# simple_ladder_filter.net
KiCad netlist of a schematic drawn in EAGLE
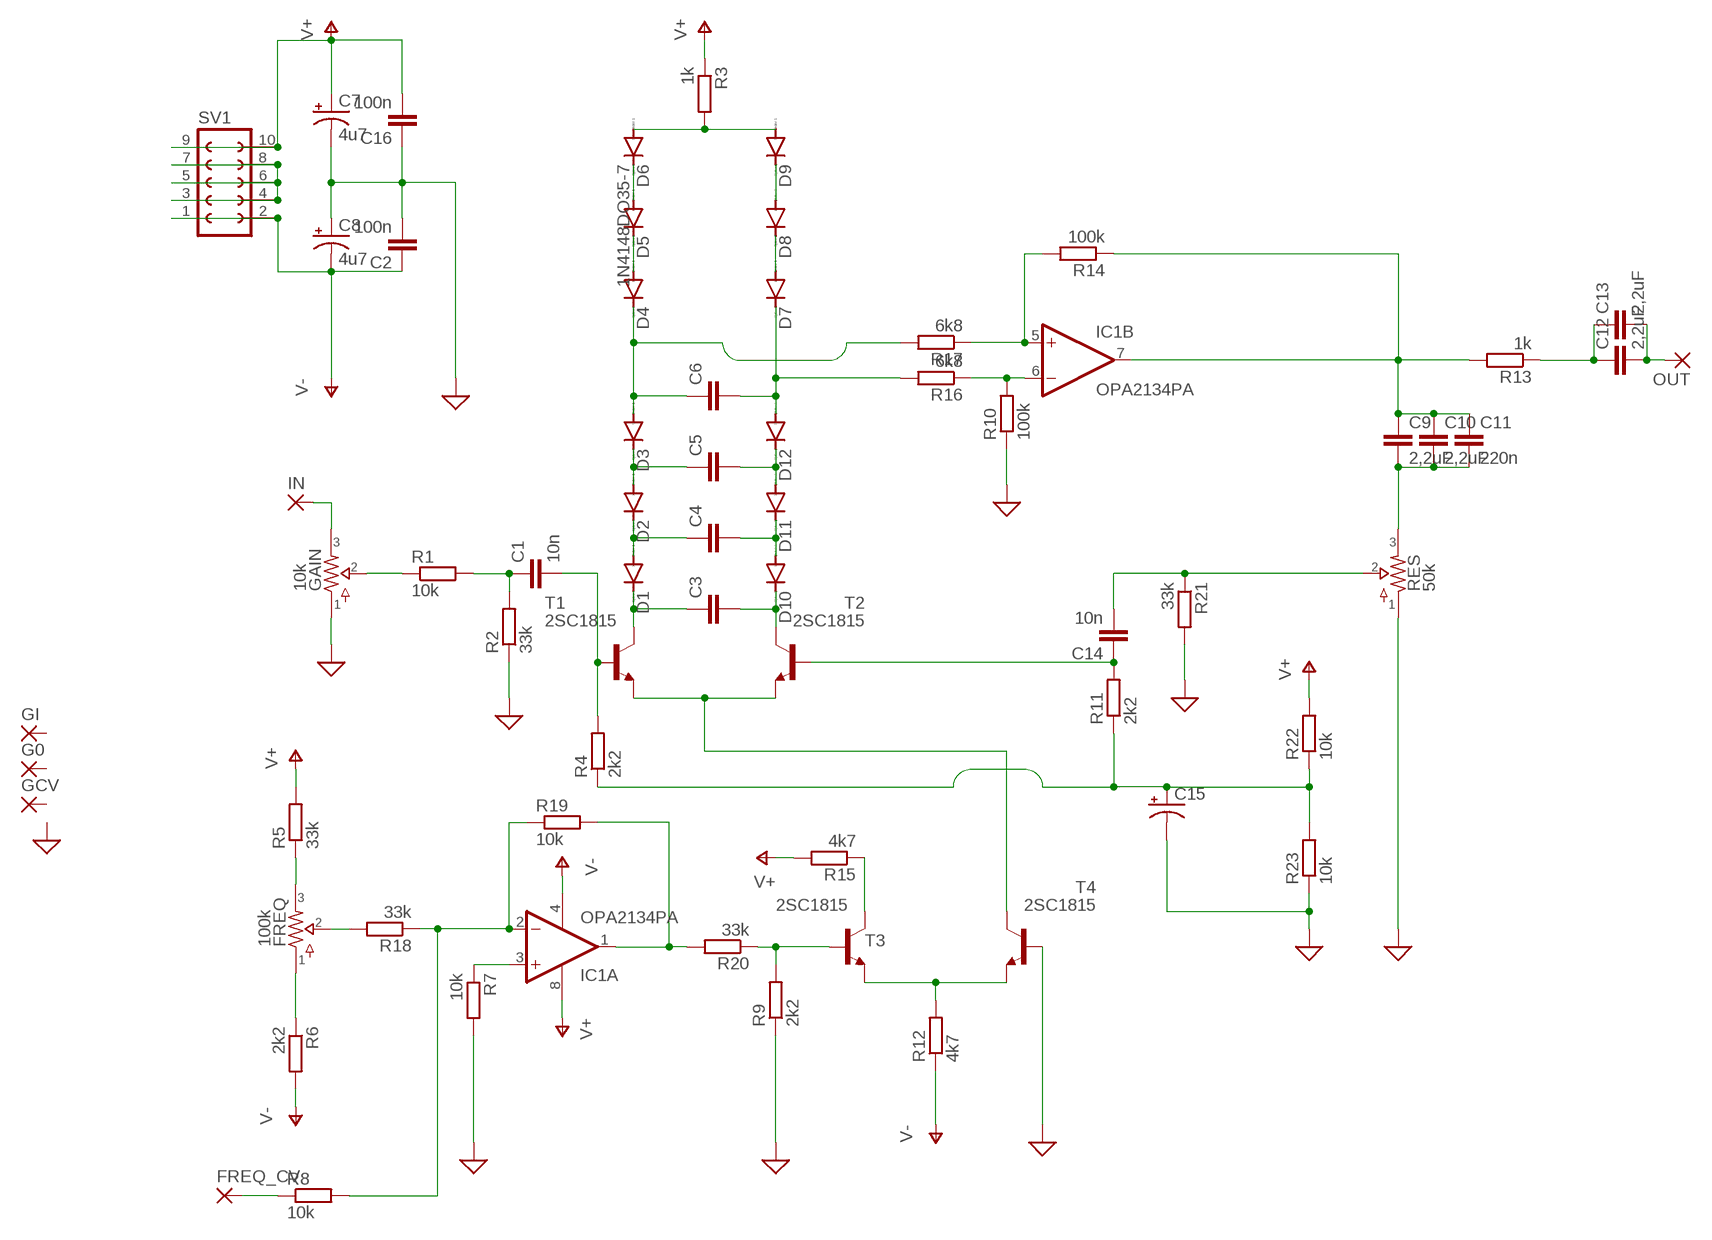
[diagram p0: schematic, sheet 1]

(export (version "E")
  (design (tool "Eeschema 10.0.6"))
  (components
    (comp (ref "C1")
      (value "10n")
      (footprint "eagle-import:C5B3")
      (libsource (lib "eagle-import") (part "C5/3"))
    )
    (comp (ref "C2")
      (value "100n")
      (footprint "eagle-import:C5B3")
      (libsource (lib "eagle-import") (part "C5/3"))
    )
    (comp (ref "C3")
      (value "C2.5/2")
      (footprint "eagle-import:C2.5-2")
      (libsource (lib "eagle-import") (part "C2.5/2"))
    )
    (comp (ref "C4")
      (value "C2.5/2")
      (footprint "eagle-import:C2.5-2")
      (libsource (lib "eagle-import") (part "C2.5/2"))
    )
    (comp (ref "C5")
      (value "C2.5/2")
      (footprint "eagle-import:C2.5-2")
      (libsource (lib "eagle-import") (part "C2.5/2"))
    )
    (comp (ref "C6")
      (value "C2.5/2")
      (footprint "eagle-import:C2.5-2")
      (libsource (lib "eagle-import") (part "C2.5/2"))
    )
    (comp (ref "C7")
      (value "4u7")
      (footprint "eagle-import:E2-4")
      (libsource (lib "eagle-import") (part "CPOL-USE2-4"))
    )
    (comp (ref "C8")
      (value "4u7")
      (footprint "eagle-import:E2-4")
      (libsource (lib "eagle-import") (part "CPOL-USE2-4"))
    )
    (comp (ref "C9")
      (value "2,2uF")
      (footprint "eagle-import:C5B5.5")
      (libsource (lib "eagle-import") (part "C5/5.5"))
    )
    (comp (ref "C10")
      (value "2,2uF")
      (footprint "eagle-import:C5B5.5")
      (libsource (lib "eagle-import") (part "C5/5.5"))
    )
    (comp (ref "C11")
      (value "220n")
      (footprint "eagle-import:C5B3")
      (libsource (lib "eagle-import") (part "C5/3"))
    )
    (comp (ref "C12")
      (value "2,2uF")
      (footprint "eagle-import:C5B5.5")
      (libsource (lib "eagle-import") (part "C5/5.5"))
    )
    (comp (ref "C13")
      (value "2,2uF")
      (footprint "eagle-import:C5B5.5")
      (libsource (lib "eagle-import") (part "C5/5.5"))
    )
    (comp (ref "C14")
      (value "10n")
      (footprint "eagle-import:C5B3")
      (libsource (lib "eagle-import") (part "C5/3"))
    )
    (comp (ref "C15")
      (value "CPOL-USE2-4")
      (footprint "eagle-import:E2-4")
      (libsource (lib "eagle-import") (part "CPOL-USE2-4"))
    )
    (comp (ref "C16")
      (value "100n")
      (footprint "eagle-import:C5B3")
      (libsource (lib "eagle-import") (part "C5/3"))
    )
    (comp (ref "D1")
      (value "1N4148DO35-7")
      (footprint "eagle-import:DO35-7")
      (libsource (lib "eagle-import") (part "1N4148DO35-7"))
    )
    (comp (ref "D2")
      (value "1N4148DO35-7")
      (footprint "eagle-import:DO35-7")
      (libsource (lib "eagle-import") (part "1N4148DO35-7"))
    )
    (comp (ref "D3")
      (value "1N4148DO35-7")
      (footprint "eagle-import:DO35-7")
      (libsource (lib "eagle-import") (part "1N4148DO35-7"))
    )
    (comp (ref "D4")
      (value "1N4148DO35-7")
      (footprint "eagle-import:DO35-7")
      (libsource (lib "eagle-import") (part "1N4148DO35-7"))
    )
    (comp (ref "D5")
      (value "1N4148DO35-7")
      (footprint "eagle-import:DO35-7")
      (libsource (lib "eagle-import") (part "1N4148DO35-7"))
    )
    (comp (ref "D6")
      (value "1N4148DO35-7")
      (footprint "eagle-import:DO35-7")
      (libsource (lib "eagle-import") (part "1N4148DO35-7"))
    )
    (comp (ref "D7")
      (value "1N4148DO35-7")
      (footprint "eagle-import:DO35-7")
      (libsource (lib "eagle-import") (part "1N4148DO35-7"))
    )
    (comp (ref "D8")
      (value "1N4148DO35-7")
      (footprint "eagle-import:DO35-7")
      (libsource (lib "eagle-import") (part "1N4148DO35-7"))
    )
    (comp (ref "D9")
      (value "1N4148DO35-7")
      (footprint "eagle-import:DO35-7")
      (libsource (lib "eagle-import") (part "1N4148DO35-7"))
    )
    (comp (ref "D10")
      (value "1N4148DO35-7")
      (footprint "eagle-import:DO35-7")
      (libsource (lib "eagle-import") (part "1N4148DO35-7"))
    )
    (comp (ref "D11")
      (value "1N4148DO35-7")
      (footprint "eagle-import:DO35-7")
      (libsource (lib "eagle-import") (part "1N4148DO35-7"))
    )
    (comp (ref "D12")
      (value "1N4148DO35-7")
      (footprint "eagle-import:DO35-7")
      (libsource (lib "eagle-import") (part "1N4148DO35-7"))
    )
    (comp (ref "FREQ")
      (value "100k")
      (footprint "eagle-import:9MM_VERT")
      (libsource (lib "eagle-import") (part "POTS9MM_VERT"))
    )
    (comp (ref "FREQ_CV")
      (value "1,6/0,9")
      (footprint "eagle-import:1,6_0,9")
      (libsource (lib "eagle-import") (part "1,6/0,9"))
    )
    (comp (ref "G0")
      (value "1,6/0,9")
      (footprint "eagle-import:1,6_0,9")
      (libsource (lib "eagle-import") (part "1,6/0,9"))
    )
    (comp (ref "GAIN")
      (value "10k")
      (footprint "eagle-import:9MM_VERT")
      (libsource (lib "eagle-import") (part "POTS9MM_VERT"))
    )
    (comp (ref "GCV")
      (value "1,6/0,9")
      (footprint "eagle-import:1,6_0,9")
      (libsource (lib "eagle-import") (part "1,6/0,9"))
    )
    (comp (ref "GI")
      (value "1,6/0,9")
      (footprint "eagle-import:1,6_0,9")
      (libsource (lib "eagle-import") (part "1,6/0,9"))
    )
    (comp (ref "IC1")
      (value "OPA2134PA")
      (footprint "eagle-import:DIL08")
      (libsource (lib "eagle-import") (part "OPA2PA134"))
    )
    (comp (ref "IN")
      (value "1,6/0,9")
      (footprint "eagle-import:1,6_0,9")
      (libsource (lib "eagle-import") (part "1,6/0,9"))
    )
    (comp (ref "OUT")
      (value "1,6/0,9")
      (footprint "eagle-import:1,6_0,9")
      (libsource (lib "eagle-import") (part "1,6/0,9"))
    )
    (comp (ref "R1")
      (value "10k")
      (footprint "eagle-import:0204_7")
      (libsource (lib "eagle-import") (part "R-EU_0204/7"))
    )
    (comp (ref "R2")
      (value "33k")
      (footprint "eagle-import:0204_7")
      (libsource (lib "eagle-import") (part "R-EU_0204/7"))
    )
    (comp (ref "R3")
      (value "1k")
      (footprint "eagle-import:0204_7")
      (libsource (lib "eagle-import") (part "R-EU_0204/7"))
    )
    (comp (ref "R4")
      (value "2k2")
      (footprint "eagle-import:0204_7")
      (libsource (lib "eagle-import") (part "R-EU_0204/7"))
    )
    (comp (ref "R5")
      (value "33k")
      (footprint "eagle-import:0204_7")
      (libsource (lib "eagle-import") (part "R-EU_0204/7"))
    )
    (comp (ref "R6")
      (value "2k2")
      (footprint "eagle-import:0204_7")
      (libsource (lib "eagle-import") (part "R-EU_0204/7"))
    )
    (comp (ref "R7")
      (value "10k")
      (footprint "eagle-import:0204_7")
      (libsource (lib "eagle-import") (part "R-EU_0204/7"))
    )
    (comp (ref "R8")
      (value "10k")
      (footprint "eagle-import:0204_7")
      (libsource (lib "eagle-import") (part "R-EU_0204/7"))
    )
    (comp (ref "R9")
      (value "2k2")
      (footprint "eagle-import:0204_7")
      (libsource (lib "eagle-import") (part "R-EU_0204/7"))
    )
    (comp (ref "R10")
      (value "100k")
      (footprint "eagle-import:0204_7")
      (libsource (lib "eagle-import") (part "R-EU_0204/7"))
    )
    (comp (ref "R11")
      (value "2k2")
      (footprint "eagle-import:0204_7")
      (libsource (lib "eagle-import") (part "R-EU_0204/7"))
    )
    (comp (ref "R12")
      (value "4k7")
      (footprint "eagle-import:0204_7")
      (libsource (lib "eagle-import") (part "R-EU_0204/7"))
    )
    (comp (ref "R13")
      (value "1k")
      (footprint "eagle-import:0204_7")
      (libsource (lib "eagle-import") (part "R-EU_0204/7"))
    )
    (comp (ref "R14")
      (value "100k")
      (footprint "eagle-import:0204_7")
      (libsource (lib "eagle-import") (part "R-EU_0204/7"))
    )
    (comp (ref "R15")
      (value "4k7")
      (footprint "eagle-import:0204_7")
      (libsource (lib "eagle-import") (part "R-EU_0204/7"))
    )
    (comp (ref "R16")
      (value "6k8")
      (footprint "eagle-import:0204_7")
      (libsource (lib "eagle-import") (part "R-EU_0204/7"))
    )
    (comp (ref "R17")
      (value "6k8")
      (footprint "eagle-import:0204_7")
      (libsource (lib "eagle-import") (part "R-EU_0204/7"))
    )
    (comp (ref "R18")
      (value "33k")
      (footprint "eagle-import:0204_7")
      (libsource (lib "eagle-import") (part "R-EU_0204/7"))
    )
    (comp (ref "R19")
      (value "10k")
      (footprint "eagle-import:0204_7")
      (libsource (lib "eagle-import") (part "R-EU_0204/7"))
    )
    (comp (ref "R20")
      (value "33k")
      (footprint "eagle-import:0204_7")
      (libsource (lib "eagle-import") (part "R-EU_0204/7"))
    )
    (comp (ref "R21")
      (value "33k")
      (footprint "eagle-import:0204_7")
      (libsource (lib "eagle-import") (part "R-EU_0204/7"))
    )
    (comp (ref "R22")
      (value "10k")
      (footprint "eagle-import:0204_7")
      (libsource (lib "eagle-import") (part "R-EU_0204/7"))
    )
    (comp (ref "R23")
      (value "10k")
      (footprint "eagle-import:0204_7")
      (libsource (lib "eagle-import") (part "R-EU_0204/7"))
    )
    (comp (ref "RES")
      (value "50k")
      (footprint "eagle-import:9MM_VERT")
      (libsource (lib "eagle-import") (part "POTS9MM_VERT"))
    )
    (comp (ref "SV1")
      (value "FE05-2")
      (footprint "eagle-import:FE05-2")
      (libsource (lib "eagle-import") (part "FE05-2"))
    )
    (comp (ref "T1")
      (value "2SC1815")
      (footprint "eagle-import:TO92-ECB")
      (libsource (lib "eagle-import") (part "2SC1815"))
    )
    (comp (ref "T2")
      (value "2SC1815")
      (footprint "eagle-import:TO92-ECB")
      (libsource (lib "eagle-import") (part "2SC1815"))
    )
    (comp (ref "T3")
      (value "2SC1815")
      (footprint "eagle-import:TO92-ECB")
      (libsource (lib "eagle-import") (part "2SC1815"))
    )
    (comp (ref "T4")
      (value "2SC1815")
      (footprint "eagle-import:TO92-ECB")
      (libsource (lib "eagle-import") (part "2SC1815"))
    )
  )
  (nets
    (net (code "1") (name "Net-(C1-Pad1)") (class "Default")
      (node (ref "C1") (pin "1") (pinfunction "1_1") (pintype "passive"))
      (node (ref "R1") (pin "2") (pinfunction "2_2") (pintype "passive"))
      (node (ref "R2") (pin "2") (pinfunction "2_2") (pintype "passive"))
    )
    (net (code "2") (name "Net-(C1-Pad2)") (class "Default")
      (node (ref "C1") (pin "2") (pinfunction "2_2") (pintype "passive"))
      (node (ref "R4") (pin "2") (pinfunction "2_2") (pintype "passive"))
      (node (ref "T1") (pin "B") (pinfunction "B_B") (pintype "passive"))
    )
    (net (code "3") (name "Net-(C3-Pad1)") (class "Default")
      (node (ref "C3") (pin "1") (pinfunction "1_1") (pintype "passive"))
      (node (ref "D1") (pin "C") (pinfunction "C_C") (pintype "passive"))
      (node (ref "T1") (pin "C") (pinfunction "C_C") (pintype "passive"))
    )
    (net (code "4") (name "Net-(C3-Pad2)") (class "Default")
      (node (ref "C3") (pin "2") (pinfunction "2_2") (pintype "passive"))
      (node (ref "D10") (pin "C") (pinfunction "C_C") (pintype "passive"))
      (node (ref "T2") (pin "C") (pinfunction "C_C") (pintype "passive"))
    )
    (net (code "5") (name "Net-(C4-Pad1)") (class "Default")
      (node (ref "C4") (pin "1") (pinfunction "1_1") (pintype "passive"))
      (node (ref "D1") (pin "A") (pinfunction "A_A") (pintype "passive"))
      (node (ref "D2") (pin "C") (pinfunction "C_C") (pintype "passive"))
    )
    (net (code "6") (name "Net-(C4-Pad2)") (class "Default")
      (node (ref "C4") (pin "2") (pinfunction "2_2") (pintype "passive"))
      (node (ref "D10") (pin "A") (pinfunction "A_A") (pintype "passive"))
      (node (ref "D11") (pin "C") (pinfunction "C_C") (pintype "passive"))
    )
    (net (code "7") (name "Net-(C5-Pad1)") (class "Default")
      (node (ref "C5") (pin "1") (pinfunction "1_1") (pintype "passive"))
      (node (ref "D2") (pin "A") (pinfunction "A_A") (pintype "passive"))
      (node (ref "D3") (pin "C") (pinfunction "C_C") (pintype "passive"))
    )
    (net (code "8") (name "Net-(C5-Pad2)") (class "Default")
      (node (ref "C5") (pin "2") (pinfunction "2_2") (pintype "passive"))
      (node (ref "D11") (pin "A") (pinfunction "A_A") (pintype "passive"))
      (node (ref "D12") (pin "C") (pinfunction "C_C") (pintype "passive"))
    )
    (net (code "9") (name "Net-(C6-Pad1)") (class "Default")
      (node (ref "C6") (pin "1") (pinfunction "1_1") (pintype "passive"))
      (node (ref "D3") (pin "A") (pinfunction "A_A") (pintype "passive"))
      (node (ref "D4") (pin "C") (pinfunction "C_C") (pintype "passive"))
      (node (ref "R17") (pin "2") (pinfunction "2_2") (pintype "passive"))
    )
    (net (code "10") (name "Net-(C6-Pad2)") (class "Default")
      (node (ref "C6") (pin "2") (pinfunction "2_2") (pintype "passive"))
      (node (ref "D12") (pin "A") (pinfunction "A_A") (pintype "passive"))
      (node (ref "D7") (pin "C") (pinfunction "C_C") (pintype "passive"))
      (node (ref "R16") (pin "2") (pinfunction "2_2") (pintype "passive"))
    )
    (net (code "11") (name "Net-(C10-Pad2)") (class "Default")
      (node (ref "C10") (pin "2") (pinfunction "2_2") (pintype "passive"))
      (node (ref "C11") (pin "2") (pinfunction "2_2") (pintype "passive"))
      (node (ref "C9") (pin "2") (pinfunction "2_2") (pintype "passive"))
      (node (ref "RES") (pin "3") (pinfunction "3_3") (pintype "passive"))
    )
    (net (code "12") (name "Net-(C12-Pad1)") (class "Default")
      (node (ref "C12") (pin "1") (pinfunction "1_1") (pintype "passive"))
      (node (ref "C13") (pin "1") (pinfunction "1_1") (pintype "passive"))
      (node (ref "R13") (pin "1") (pinfunction "1_1") (pintype "passive"))
    )
    (net (code "13") (name "Net-(C14-Pad1)") (class "Default")
      (node (ref "C14") (pin "1") (pinfunction "1_1") (pintype "passive"))
      (node (ref "R11") (pin "2") (pinfunction "2_2") (pintype "passive"))
      (node (ref "T2") (pin "B") (pinfunction "B_B") (pintype "passive"))
    )
    (net (code "14") (name "Net-(C14-Pad2)") (class "Default")
      (node (ref "C14") (pin "2") (pinfunction "2_2") (pintype "passive"))
      (node (ref "R21") (pin "1") (pinfunction "1_1") (pintype "passive"))
      (node (ref "RES") (pin "2") (pinfunction "2_2") (pintype "passive"))
    )
    (net (code "15") (name "Net-(C15-Pad+)") (class "Default")
      (node (ref "C15") (pin "+") (pinfunction "+_+") (pintype "passive"))
      (node (ref "R11") (pin "1") (pinfunction "1_1") (pintype "passive"))
      (node (ref "R22") (pin "1") (pinfunction "1_1") (pintype "passive"))
      (node (ref "R23") (pin "2") (pinfunction "2_2") (pintype "passive"))
      (node (ref "R4") (pin "1") (pinfunction "1_1") (pintype "passive"))
    )
    (net (code "16") (name "Net-(D4-PadA)") (class "Default")
      (node (ref "D4") (pin "A") (pinfunction "A_A") (pintype "passive"))
      (node (ref "D5") (pin "C") (pinfunction "C_C") (pintype "passive"))
    )
    (net (code "17") (name "Net-(D5-PadA)") (class "Default")
      (node (ref "D5") (pin "A") (pinfunction "A_A") (pintype "passive"))
      (node (ref "D6") (pin "C") (pinfunction "C_C") (pintype "passive"))
    )
    (net (code "18") (name "Net-(D6-PadA)") (class "Default")
      (node (ref "D6") (pin "A") (pinfunction "A_A") (pintype "passive"))
      (node (ref "D9") (pin "A") (pinfunction "A_A") (pintype "passive"))
      (node (ref "R3") (pin "2") (pinfunction "2_2") (pintype "passive"))
    )
    (net (code "19") (name "Net-(D7-PadA)") (class "Default")
      (node (ref "D7") (pin "A") (pinfunction "A_A") (pintype "passive"))
      (node (ref "D8") (pin "C") (pinfunction "C_C") (pintype "passive"))
    )
    (net (code "20") (name "Net-(D8-PadA)") (class "Default")
      (node (ref "D8") (pin "A") (pinfunction "A_A") (pintype "passive"))
      (node (ref "D9") (pin "C") (pinfunction "C_C") (pintype "passive"))
    )
    (net (code "21") (name "Net-(FREQ-Pad1)") (class "Default")
      (node (ref "FREQ") (pin "1") (pinfunction "1_1") (pintype "passive"))
      (node (ref "R6") (pin "1") (pinfunction "1_1") (pintype "passive"))
    )
    (net (code "22") (name "Net-(FREQ-Pad2)") (class "Default")
      (node (ref "FREQ") (pin "2") (pinfunction "2_2") (pintype "passive"))
      (node (ref "R18") (pin "2") (pinfunction "2_2") (pintype "passive"))
    )
    (net (code "23") (name "Net-(FREQ-Pad3)") (class "Default")
      (node (ref "FREQ") (pin "3") (pinfunction "3_3") (pintype "passive"))
      (node (ref "R5") (pin "1") (pinfunction "1_1") (pintype "passive"))
    )
    (net (code "24") (name "Net-(FREQ_CV-P)") (class "Default")
      (node (ref "FREQ_CV") (pin "1") (pinfunction "P_1") (pintype "passive"))
      (node (ref "R8") (pin "1") (pinfunction "1_1") (pintype "passive"))
    )
    (net (code "25") (name "Net-(GAIN-Pad2)") (class "Default")
      (node (ref "GAIN") (pin "2") (pinfunction "2_2") (pintype "passive"))
      (node (ref "R1") (pin "1") (pinfunction "1_1") (pintype "passive"))
    )
    (net (code "26") (name "Net-(IC1A-+IN)") (class "Default")
      (node (ref "IC1") (pin "3") (pinfunction "+IN_3") (pintype "input"))
      (node (ref "R7") (pin "1") (pinfunction "1_1") (pintype "passive"))
    )
    (net (code "27") (name "Net-(IC1A--IN)") (class "Default")
      (node (ref "IC1") (pin "2") (pinfunction "-IN_2") (pintype "input"))
      (node (ref "R18") (pin "1") (pinfunction "1_1") (pintype "passive"))
      (node (ref "R19") (pin "1") (pinfunction "1_1") (pintype "passive"))
      (node (ref "R8") (pin "2") (pinfunction "2_2") (pintype "passive"))
    )
    (net (code "28") (name "Net-(IC1A-OUT)") (class "Default")
      (node (ref "IC1") (pin "1") (pinfunction "OUT_1") (pintype "output"))
      (node (ref "R19") (pin "2") (pinfunction "2_2") (pintype "passive"))
      (node (ref "R20") (pin "2") (pinfunction "2_2") (pintype "passive"))
    )
    (net (code "29") (name "Net-(IC1B-+IN)") (class "Default")
      (node (ref "IC1") (pin "5") (pinfunction "+IN_5") (pintype "input"))
      (node (ref "R14") (pin "2") (pinfunction "2_2") (pintype "passive"))
      (node (ref "R17") (pin "1") (pinfunction "1_1") (pintype "passive"))
    )
    (net (code "30") (name "Net-(IC1B--IN)") (class "Default")
      (node (ref "IC1") (pin "6") (pinfunction "-IN_6") (pintype "input"))
      (node (ref "R10") (pin "2") (pinfunction "2_2") (pintype "passive"))
      (node (ref "R16") (pin "1") (pinfunction "1_1") (pintype "passive"))
    )
    (net (code "31") (name "Net-(IC1B-OUT)") (class "Default")
      (node (ref "C10") (pin "1") (pinfunction "1_1") (pintype "passive"))
      (node (ref "C11") (pin "1") (pinfunction "1_1") (pintype "passive"))
      (node (ref "C9") (pin "1") (pinfunction "1_1") (pintype "passive"))
      (node (ref "IC1") (pin "7") (pinfunction "OUT_7") (pintype "output"))
      (node (ref "R13") (pin "2") (pinfunction "2_2") (pintype "passive"))
      (node (ref "R14") (pin "1") (pinfunction "1_1") (pintype "passive"))
    )
    (net (code "32") (name "Net-(IN-P)") (class "Default")
      (node (ref "GAIN") (pin "3") (pinfunction "3_3") (pintype "passive"))
      (node (ref "IN") (pin "1") (pinfunction "P_1") (pintype "passive"))
    )
    (net (code "33") (name "Net-(OUT-P)") (class "Default")
      (node (ref "C12") (pin "2") (pinfunction "2_2") (pintype "passive"))
      (node (ref "C13") (pin "2") (pinfunction "2_2") (pintype "passive"))
      (node (ref "OUT") (pin "1") (pinfunction "P_1") (pintype "passive"))
    )
    (net (code "34") (name "Net-(R12-Pad2)") (class "Default")
      (node (ref "R12") (pin "2") (pinfunction "2_2") (pintype "passive"))
      (node (ref "T3") (pin "E") (pinfunction "E_E") (pintype "passive"))
      (node (ref "T4") (pin "E") (pinfunction "E_E") (pintype "passive"))
    )
    (net (code "35") (name "Net-(R15-Pad1)") (class "Default")
      (node (ref "R15") (pin "1") (pinfunction "1_1") (pintype "passive"))
      (node (ref "T3") (pin "C") (pinfunction "C_C") (pintype "passive"))
    )
    (net (code "36") (name "Net-(R20-Pad1)") (class "Default")
      (node (ref "R20") (pin "1") (pinfunction "1_1") (pintype "passive"))
      (node (ref "R9") (pin "2") (pinfunction "2_2") (pintype "passive"))
      (node (ref "T3") (pin "B") (pinfunction "B_B") (pintype "passive"))
    )
    (net (code "37") (name "Net-(SV1-Pad3)") (class "Default")
      (node (ref "SV1") (pin "3") (pinfunction "3_3") (pintype "passive"))
      (node (ref "SV1") (pin "4") (pinfunction "4_4") (pintype "passive"))
      (node (ref "SV1") (pin "5") (pinfunction "5_5") (pintype "passive"))
      (node (ref "SV1") (pin "6") (pinfunction "6_6") (pintype "passive"))
      (node (ref "SV1") (pin "7") (pinfunction "7_7") (pintype "passive"))
      (node (ref "SV1") (pin "8") (pinfunction "8_8") (pintype "passive"))
    )
    (net (code "38") (name "Net-(T1-PadE)") (class "Default")
      (node (ref "T1") (pin "E") (pinfunction "E_E") (pintype "passive"))
      (node (ref "T2") (pin "E") (pinfunction "E_E") (pintype "passive"))
      (node (ref "T4") (pin "C") (pinfunction "C_C") (pintype "passive"))
    )
    (net (code "39") (name "SUP") (class "Default")
      (node (ref "C15") (pin "-") (pinfunction "-_-") (pintype "passive"))
      (node (ref "C16") (pin "1") (pinfunction "1_1") (pintype "passive"))
      (node (ref "C2") (pin "2") (pinfunction "2_2") (pintype "passive"))
      (node (ref "C7") (pin "-") (pinfunction "-_-") (pintype "passive"))
      (node (ref "C8") (pin "+") (pinfunction "+_+") (pintype "passive"))
      (node (ref "GAIN") (pin "1") (pinfunction "1_1") (pintype "passive"))
      (node (ref "R10") (pin "1") (pinfunction "1_1") (pintype "passive"))
      (node (ref "R2") (pin "1") (pinfunction "1_1") (pintype "passive"))
      (node (ref "R21") (pin "2") (pinfunction "2_2") (pintype "passive"))
      (node (ref "R23") (pin "1") (pinfunction "1_1") (pintype "passive"))
      (node (ref "R7") (pin "2") (pinfunction "2_2") (pintype "passive"))
      (node (ref "R9") (pin "1") (pinfunction "1_1") (pintype "passive"))
      (node (ref "RES") (pin "1") (pinfunction "1_1") (pintype "passive"))
      (node (ref "T4") (pin "B") (pinfunction "B_B") (pintype "passive"))
    )
    (net (code "40") (name "V+") (class "Default")
      (node (ref "C16") (pin "2") (pinfunction "2_2") (pintype "passive"))
      (node (ref "C7") (pin "+") (pinfunction "+_+") (pintype "passive"))
      (node (ref "IC1") (pin "8") (pinfunction "V+_8") (pintype "power_in"))
      (node (ref "R15") (pin "2") (pinfunction "2_2") (pintype "passive"))
      (node (ref "R22") (pin "2") (pinfunction "2_2") (pintype "passive"))
      (node (ref "R3") (pin "1") (pinfunction "1_1") (pintype "passive"))
      (node (ref "R5") (pin "2") (pinfunction "2_2") (pintype "passive"))
      (node (ref "SV1") (pin "10") (pinfunction "10_10") (pintype "passive"))
      (node (ref "SV1") (pin "9") (pinfunction "9_9") (pintype "passive"))
    )
    (net (code "41") (name "V-") (class "Default")
      (node (ref "C2") (pin "1") (pinfunction "1_1") (pintype "passive"))
      (node (ref "C8") (pin "-") (pinfunction "-_-") (pintype "passive"))
      (node (ref "IC1") (pin "4") (pinfunction "V-_4") (pintype "power_in"))
      (node (ref "R12") (pin "1") (pinfunction "1_1") (pintype "passive"))
      (node (ref "R6") (pin "2") (pinfunction "2_2") (pintype "passive"))
      (node (ref "SV1") (pin "1") (pinfunction "1_1") (pintype "passive"))
      (node (ref "SV1") (pin "2") (pinfunction "2_2") (pintype "passive"))
    )
    (net (code "42") (name "unconnected-(G0-P-Pad1)") (class "Default")
      (node (ref "G0") (pin "1") (pinfunction "P_1") (pintype "passive"))
    )
    (net (code "43") (name "unconnected-(GCV-P-Pad1)") (class "Default")
      (node (ref "GCV") (pin "1") (pinfunction "P_1") (pintype "passive"))
    )
    (net (code "44") (name "unconnected-(GI-P-Pad1)") (class "Default")
      (node (ref "GI") (pin "1") (pinfunction "P_1") (pintype "passive"))
    )
  )
)
